# 2008_SablierElectronique_Alim.net
KiCad netlist of a schematic drawn in Altium Designer
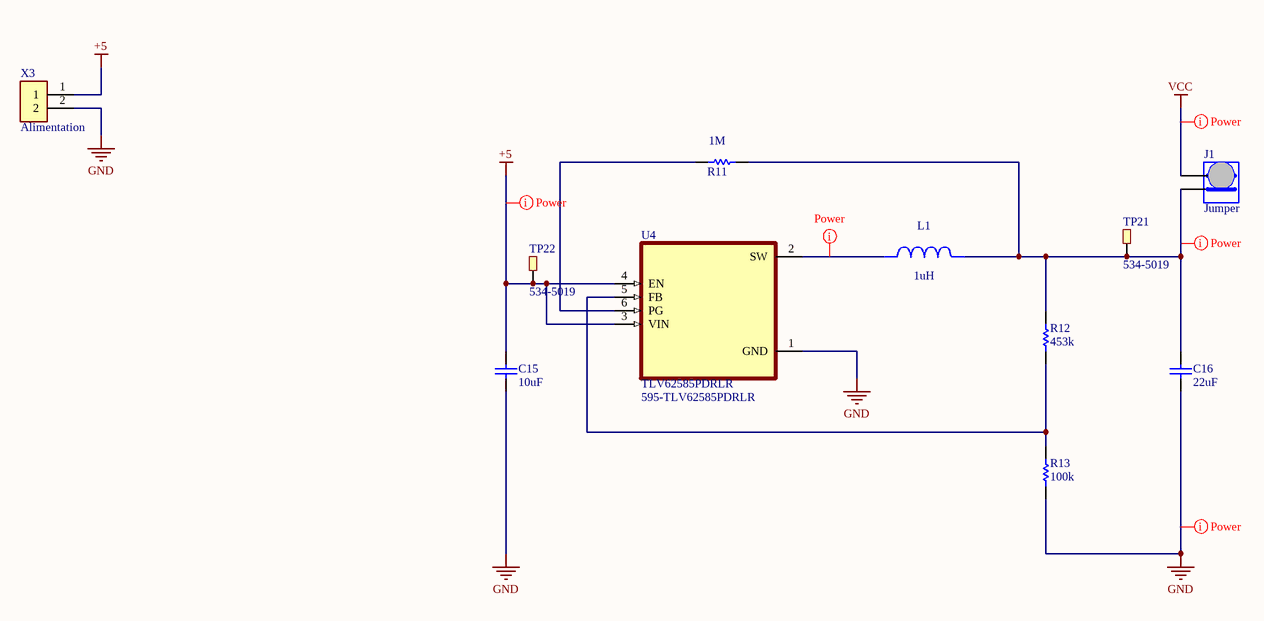
[diagram p0: 2008_SablierElectronique_Alim.SchDoc]

(export (version "E")
  (design (tool "Eeschema 10.0.6"))
  (components
    (comp (ref "C15")
      (value "10uF")
      (footprint "RESC0805(2012)_L")
      (libsource (lib "2008_SablierElectronique_SCHLIB") (part "CAP1206"))
    )
    (comp (ref "C16")
      (value "22uF")
      (footprint "RESC0805(2012)_L")
      (libsource (lib "2008_SablierElectronique_SCHLIB") (part "CAP1206"))
    )
    (comp (ref "J1")
      (value "Jumper")
      (footprint "Jumper")
      (libsource (lib "2008_SablierElectronique_SCHLIB") (part "Jumper_2p"))
    )
    (comp (ref "L1")
      (value "1uH")
      (footprint "RESC0805(2012)_L")
      (description "LQM21PN1R0MCHD")
      (fields (field (name "Comment") "LQM21PN1R0MCHD0"))
      (libsource (lib "TI WEBENCH") (part "L1"))
    )
    (comp (ref "R11")
      (value "1M")
      (footprint "RESC0805(2012)_L")
      (libsource (lib "2008_SablierElectronique_SCHLIB") (part "RES"))
    )
    (comp (ref "R12")
      (value "453k")
      (footprint "RESC0805(2012)_L")
      (libsource (lib "2008_SablierElectronique_SCHLIB") (part "RES"))
    )
    (comp (ref "R13")
      (value "100k")
      (footprint "RESC0805(2012)_L")
      (libsource (lib "2008_SablierElectronique_SCHLIB") (part "RES"))
    )
    (comp (ref "TP21")
      (value "5019")
      (footprint "TESTPOINT_SMD")
      (description "Test point smd")
      (fields (field (name "SUPPLIER PART NUMBER 1") "534-5019"))
      (libsource (lib "2008_SablierElectronique_SCHLIB") (part "TESTPOINT"))
    )
    (comp (ref "TP22")
      (value "5019")
      (footprint "TESTPOINT_SMD")
      (description "Test point smd")
      (fields (field (name "SUPPLIER PART NUMBER 1") "534-5019"))
      (libsource (lib "2008_SablierElectronique_SCHLIB") (part "TESTPOINT"))
    )
    (comp (ref "U4")
      (value "TLV62585PDRLR")
      (footprint "SOT563")
      (fields
        (field (name "MF") "Texas Instruments")
        (field (name "SUPPLIER PART NUMBER 1") "595-TLV62585PDRLR")
      )
      (libsource (lib "2008_SablierElectronique_SCHLIB") (part "TLV62585PDRLR"))
    )
    (comp (ref "X3")
      (value "Alimentation")
      (footprint "Header 2 pin")
      (description "Connector Header Through Hole 2 position")
      (fields (field (name "MF") "TE Connectivity") (field (name "MP") "826632-1"))
      (libsource (lib "2008_SablierElectronique_SCHLIB") (part "Header 2 pin"))
    )
  )
  (nets
    (net (code "1") (name "+5") (class "Default")
      (node (ref "C15") (pin "2") (pinfunction "2_2") (pintype "passive"))
      (node (ref "TP22") (pin "1") (pinfunction "1_1") (pintype "passive"))
      (node (ref "U4") (pin "3") (pinfunction "VIN_3") (pintype "input"))
      (node (ref "U4") (pin "4") (pinfunction "EN_4") (pintype "input"))
      (node (ref "X3") (pin "1") (pinfunction "1_1") (pintype "passive"))
    )
    (net (code "2") (name "GND") (class "Default")
      (node (ref "C15") (pin "1") (pinfunction "1_1") (pintype "passive"))
      (node (ref "C16") (pin "1") (pinfunction "1_1") (pintype "passive"))
      (node (ref "R13") (pin "2") (pinfunction "2_2") (pintype "passive"))
      (node (ref "U4") (pin "1") (pinfunction "GND_1") (pintype "power_in"))
      (node (ref "X3") (pin "2") (pinfunction "2_2") (pintype "passive"))
    )
    (net (code "3") (name "Net-(C16-Pad2)") (class "Default")
      (node (ref "C16") (pin "2") (pinfunction "2_2") (pintype "passive"))
      (node (ref "J1") (pin "2") (pinfunction "2_2") (pintype "passive"))
      (node (ref "L1") (pin "1") (pinfunction "1_1") (pintype "passive"))
      (node (ref "R11") (pin "1") (pinfunction "1_1") (pintype "passive"))
      (node (ref "R12") (pin "1") (pinfunction "1_1") (pintype "passive"))
      (node (ref "TP21") (pin "1") (pinfunction "1_1") (pintype "passive"))
    )
    (net (code "4") (name "Net-(U4-FB)") (class "Default")
      (node (ref "R12") (pin "2") (pinfunction "2_2") (pintype "passive"))
      (node (ref "R13") (pin "1") (pinfunction "1_1") (pintype "passive"))
      (node (ref "U4") (pin "5") (pinfunction "FB_5") (pintype "input"))
    )
    (net (code "5") (name "Net-(U4-PG)") (class "Default")
      (node (ref "R11") (pin "2") (pinfunction "2_2") (pintype "passive"))
      (node (ref "U4") (pin "6") (pinfunction "PG_6") (pintype "input"))
    )
    (net (code "6") (name "Net-(U4-SW)") (class "Default")
      (node (ref "L1") (pin "2") (pinfunction "2_2") (pintype "passive"))
      (node (ref "U4") (pin "2") (pinfunction "SW_2") (pintype "power_in"))
    )
    (net (code "7") (name "VCC") (class "Default")
      (node (ref "J1") (pin "1") (pinfunction "1_1") (pintype "passive"))
    )
  )
)
